# SDI-synchro-drive.net
KiCad netlist of a schematic drawn in EAGLE
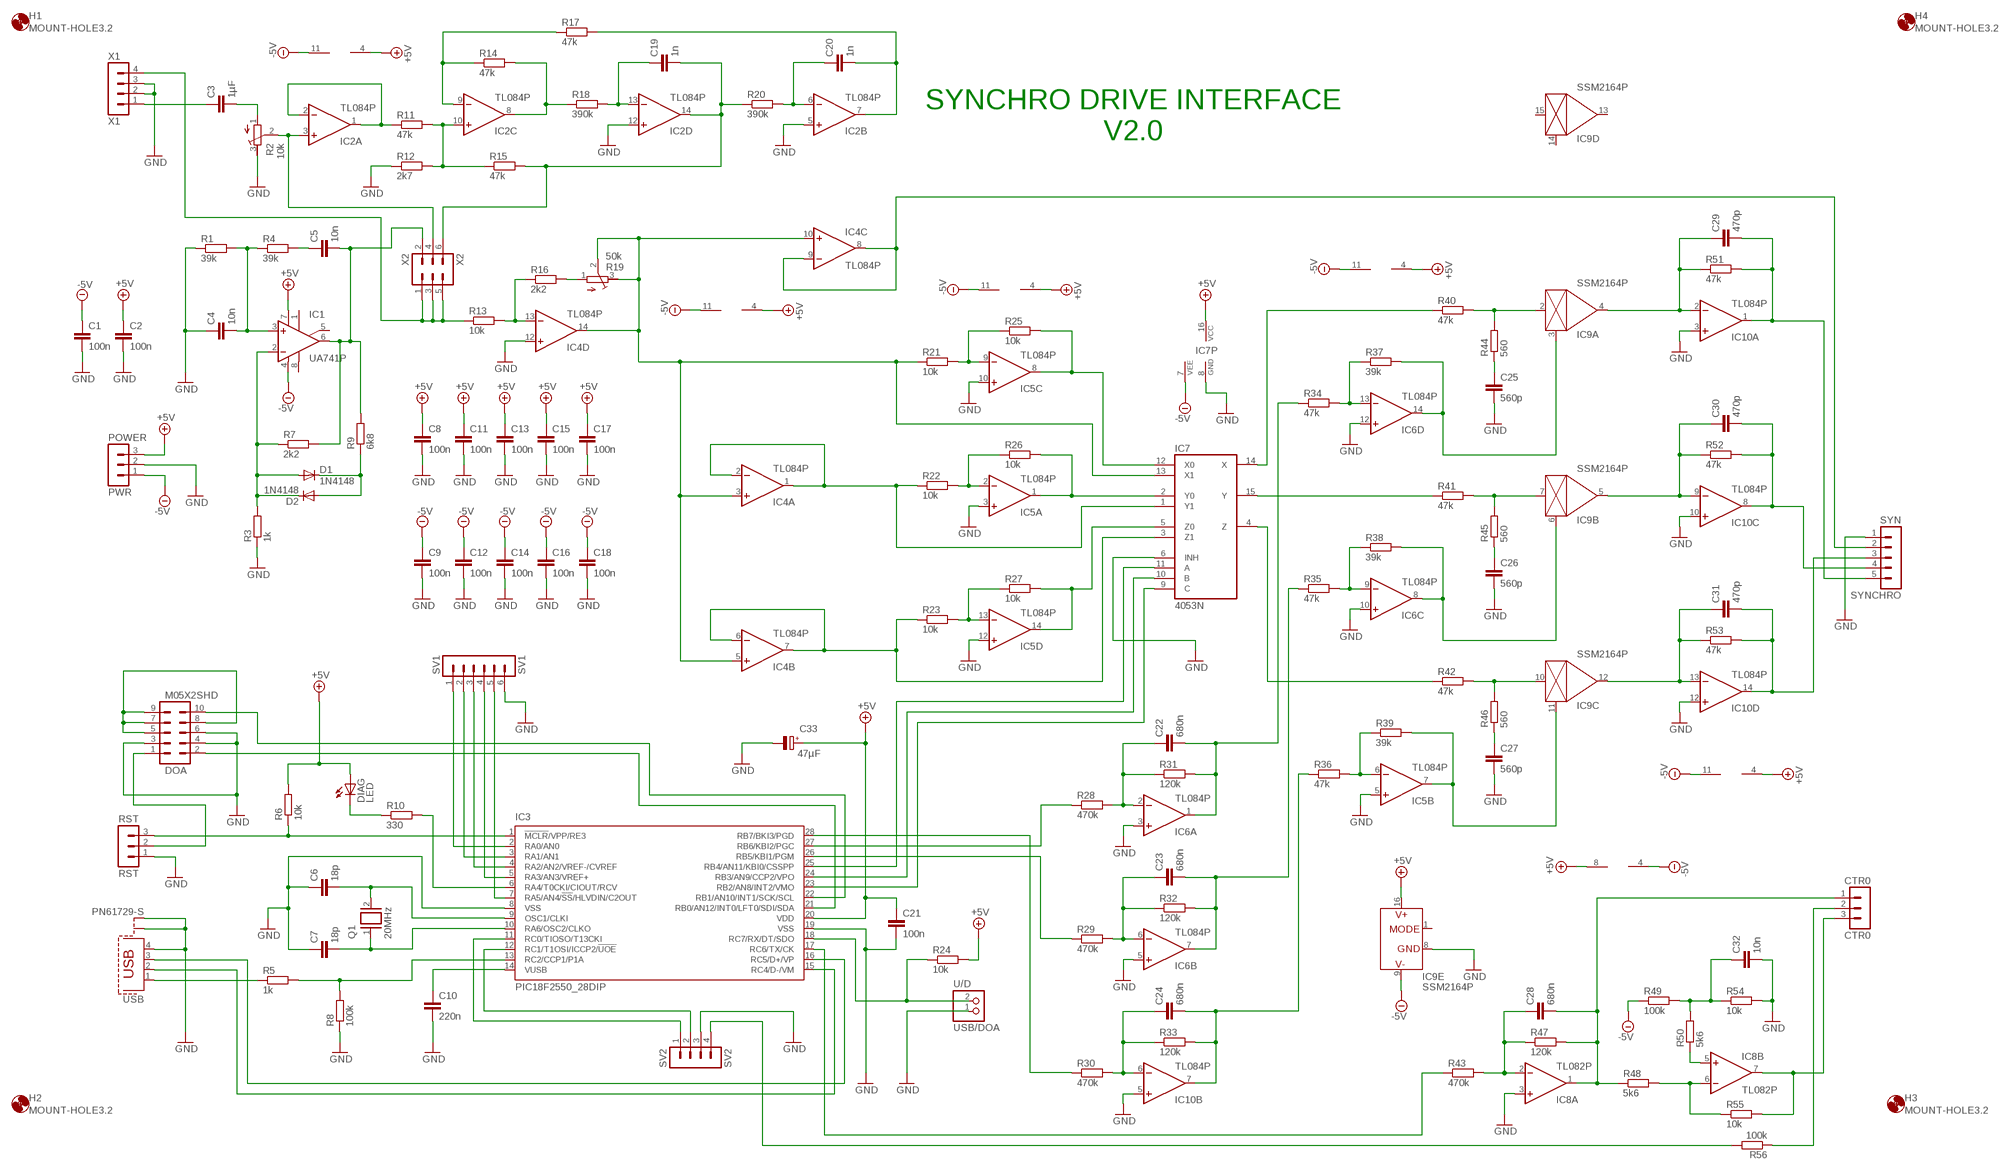
[diagram p0: schematic, sheet 1]

(export (version "E")
  (design (tool "Eeschema 10.0.6"))
  (components
    (comp (ref "C1")
      (value "100n")
      (footprint "eagle-import:C025-025X050")
      (libsource (lib "eagle-import") (part "C-EU025-025X050"))
    )
    (comp (ref "C2")
      (value "100n")
      (footprint "eagle-import:C025-025X050")
      (libsource (lib "eagle-import") (part "C-EU025-025X050"))
    )
    (comp (ref "C3")
      (value "1µF")
      (footprint "eagle-import:C5B3")
      (libsource (lib "eagle-import") (part "C5/3"))
    )
    (comp (ref "C4")
      (value "10n")
      (footprint "eagle-import:C025-025X050")
      (libsource (lib "eagle-import") (part "C-EU025-025X050"))
    )
    (comp (ref "C5")
      (value "10n")
      (footprint "eagle-import:C025-025X050")
      (libsource (lib "eagle-import") (part "C-EU025-025X050"))
    )
    (comp (ref "C6")
      (value "18p")
      (footprint "eagle-import:C025-025X050")
      (libsource (lib "eagle-import") (part "C-EU025-025X050"))
    )
    (comp (ref "C7")
      (value "18p")
      (footprint "eagle-import:C025-025X050")
      (libsource (lib "eagle-import") (part "C-EU025-025X050"))
    )
    (comp (ref "C8")
      (value "100n")
      (footprint "eagle-import:C025-025X050")
      (libsource (lib "eagle-import") (part "C-EU025-025X050"))
    )
    (comp (ref "C9")
      (value "100n")
      (footprint "eagle-import:C025-025X050")
      (libsource (lib "eagle-import") (part "C-EU025-025X050"))
    )
    (comp (ref "C10")
      (value "220n")
      (footprint "eagle-import:C5B3")
      (libsource (lib "eagle-import") (part "C5/3"))
    )
    (comp (ref "C11")
      (value "100n")
      (footprint "eagle-import:C025-025X050")
      (libsource (lib "eagle-import") (part "C-EU025-025X050"))
    )
    (comp (ref "C12")
      (value "100n")
      (footprint "eagle-import:C025-025X050")
      (libsource (lib "eagle-import") (part "C-EU025-025X050"))
    )
    (comp (ref "C13")
      (value "100n")
      (footprint "eagle-import:C025-025X050")
      (libsource (lib "eagle-import") (part "C-EU025-025X050"))
    )
    (comp (ref "C14")
      (value "100n")
      (footprint "eagle-import:C025-025X050")
      (libsource (lib "eagle-import") (part "C-EU025-025X050"))
    )
    (comp (ref "C15")
      (value "100n")
      (footprint "eagle-import:C025-025X050")
      (libsource (lib "eagle-import") (part "C-EU025-025X050"))
    )
    (comp (ref "C16")
      (value "100n")
      (footprint "eagle-import:C025-025X050")
      (libsource (lib "eagle-import") (part "C-EU025-025X050"))
    )
    (comp (ref "C17")
      (value "100n")
      (footprint "eagle-import:C025-025X050")
      (libsource (lib "eagle-import") (part "C-EU025-025X050"))
    )
    (comp (ref "C18")
      (value "100n")
      (footprint "eagle-import:C025-025X050")
      (libsource (lib "eagle-import") (part "C-EU025-025X050"))
    )
    (comp (ref "C19")
      (value "1n")
      (footprint "eagle-import:C025-025X050")
      (libsource (lib "eagle-import") (part "C-EU025-025X050"))
    )
    (comp (ref "C20")
      (value "1n")
      (footprint "eagle-import:C025-025X050")
      (libsource (lib "eagle-import") (part "C-EU025-025X050"))
    )
    (comp (ref "C21")
      (value "100n")
      (footprint "eagle-import:C025-025X050")
      (libsource (lib "eagle-import") (part "C-EU025-025X050"))
    )
    (comp (ref "C22")
      (value "680n")
      (footprint "eagle-import:C5B3")
      (libsource (lib "eagle-import") (part "C5/3"))
    )
    (comp (ref "C23")
      (value "680n")
      (footprint "eagle-import:C5B3")
      (libsource (lib "eagle-import") (part "C5/3"))
    )
    (comp (ref "C24")
      (value "680n")
      (footprint "eagle-import:C5B3")
      (libsource (lib "eagle-import") (part "C5/3"))
    )
    (comp (ref "C25")
      (value "560p")
      (footprint "eagle-import:C025-025X050")
      (libsource (lib "eagle-import") (part "C-EU025-025X050"))
    )
    (comp (ref "C26")
      (value "560p")
      (footprint "eagle-import:C025-025X050")
      (libsource (lib "eagle-import") (part "C-EU025-025X050"))
    )
    (comp (ref "C27")
      (value "560p")
      (footprint "eagle-import:C025-025X050")
      (libsource (lib "eagle-import") (part "C-EU025-025X050"))
    )
    (comp (ref "C28")
      (value "680n")
      (footprint "eagle-import:C5B3")
      (libsource (lib "eagle-import") (part "C5/3"))
    )
    (comp (ref "C29")
      (value "470p")
      (footprint "eagle-import:C025-025X050")
      (libsource (lib "eagle-import") (part "C-EU025-025X050"))
    )
    (comp (ref "C30")
      (value "470p")
      (footprint "eagle-import:C025-025X050")
      (libsource (lib "eagle-import") (part "C-EU025-025X050"))
    )
    (comp (ref "C31")
      (value "470p")
      (footprint "eagle-import:C025-025X050")
      (libsource (lib "eagle-import") (part "C-EU025-025X050"))
    )
    (comp (ref "C32")
      (value "10n")
      (footprint "eagle-import:C025-025X050")
      (libsource (lib "eagle-import") (part "C-EU025-025X050"))
    )
    (comp (ref "C33")
      (value "47µF")
      (footprint "eagle-import:E2,5-6")
      (libsource (lib "eagle-import") (part "CPOL-EUE2.5-6"))
    )
    (comp (ref "CTR0")
      (value "CTR0")
      (footprint "eagle-import:MA03-1")
      (libsource (lib "eagle-import") (part "MA03-1"))
    )
    (comp (ref "D1")
      (value "1N4148")
      (footprint "eagle-import:DO35-7")
      (libsource (lib "eagle-import") (part "1N4148DO35-7"))
    )
    (comp (ref "D2")
      (value "1N4148")
      (footprint "eagle-import:DO35-7")
      (libsource (lib "eagle-import") (part "1N4148DO35-7"))
    )
    (comp (ref "DIAG")
      (value "LED")
      (footprint "eagle-import:LED3MM")
      (libsource (lib "eagle-import") (part "LED3MM"))
    )
    (comp (ref "DOA")
      (value "M05X2SHD")
      (footprint "eagle-import:2X5-SHROUDED")
      (libsource (lib "eagle-import") (part "M05X2SHD"))
    )
    (comp (ref "H1")
      (value "MOUNT-HOLE3.2")
      (footprint "eagle-import:3,2")
      (libsource (lib "eagle-import") (part "MOUNT-HOLE3.2"))
    )
    (comp (ref "H2")
      (value "MOUNT-HOLE3.2")
      (footprint "eagle-import:3,2")
      (libsource (lib "eagle-import") (part "MOUNT-HOLE3.2"))
    )
    (comp (ref "H3")
      (value "MOUNT-HOLE3.2")
      (footprint "eagle-import:3,2")
      (libsource (lib "eagle-import") (part "MOUNT-HOLE3.2"))
    )
    (comp (ref "H4")
      (value "MOUNT-HOLE3.2")
      (footprint "eagle-import:3,2")
      (libsource (lib "eagle-import") (part "MOUNT-HOLE3.2"))
    )
    (comp (ref "IC1")
      (value "UA741P")
      (footprint "eagle-import:DIL08")
      (libsource (lib "eagle-import") (part "741PUA"))
    )
    (comp (ref "IC2")
      (value "TL084P")
      (footprint "eagle-import:DIL14")
      (libsource (lib "eagle-import") (part "TL084P"))
    )
    (comp (ref "IC3")
      (value "PIC18F2550_28DIP")
      (footprint "eagle-import:DIL28-3")
      (fields (field (name "MF") "MICROCHIP") (field (name "MPN") "PIC18F2550-I/SP"))
      (libsource (lib "eagle-import") (part "PIC18F2_28DIP550"))
    )
    (comp (ref "IC4")
      (value "TL084P")
      (footprint "eagle-import:DIL14")
      (libsource (lib "eagle-import") (part "TL084P"))
    )
    (comp (ref "IC5")
      (value "TL084P")
      (footprint "eagle-import:DIL14")
      (libsource (lib "eagle-import") (part "TL084P"))
    )
    (comp (ref "IC6")
      (value "TL084P")
      (footprint "eagle-import:DIL14")
      (libsource (lib "eagle-import") (part "TL084P"))
    )
    (comp (ref "IC7")
      (value "4053N")
      (footprint "eagle-import:DIL16")
      (libsource (lib "eagle-import") (part "4053N"))
    )
    (comp (ref "IC8")
      (value "TL082P")
      (footprint "eagle-import:DIL08")
      (libsource (lib "eagle-import") (part "TL082P"))
    )
    (comp (ref "IC9")
      (value "SSM2164P")
      (footprint "eagle-import:DIL16")
      (libsource (lib "eagle-import") (part "SSM2164P"))
    )
    (comp (ref "IC10")
      (value "TL084P")
      (footprint "eagle-import:DIL14")
      (libsource (lib "eagle-import") (part "TL084P"))
    )
    (comp (ref "POWER")
      (value "PWR")
      (footprint "eagle-import:MA03-1")
      (libsource (lib "eagle-import") (part "MA03-1"))
    )
    (comp (ref "Q1")
      (value "20MHz")
      (footprint "eagle-import:QS")
      (libsource (lib "eagle-import") (part "XTAL/S"))
    )
    (comp (ref "R1")
      (value "39k")
      (footprint "eagle-import:0204_7")
      (libsource (lib "eagle-import") (part "R-EU_0204/7"))
    )
    (comp (ref "R2")
      (value "10k")
      (footprint "eagle-import:RTRIM3299W")
      (libsource (lib "eagle-import") (part "R-TRIMM3299W"))
    )
    (comp (ref "R3")
      (value "1k")
      (footprint "eagle-import:0204_7")
      (libsource (lib "eagle-import") (part "R-EU_0204/7"))
    )
    (comp (ref "R4")
      (value "39k")
      (footprint "eagle-import:0204_7")
      (libsource (lib "eagle-import") (part "R-EU_0204/7"))
    )
    (comp (ref "R5")
      (value "1k")
      (footprint "eagle-import:0204_7")
      (libsource (lib "eagle-import") (part "R-EU_0204/7"))
    )
    (comp (ref "R6")
      (value "10k")
      (footprint "eagle-import:0204_7")
      (libsource (lib "eagle-import") (part "R-EU_0204/7"))
    )
    (comp (ref "R7")
      (value "2k2")
      (footprint "eagle-import:0204_7")
      (libsource (lib "eagle-import") (part "R-EU_0204/7"))
    )
    (comp (ref "R8")
      (value "100k")
      (footprint "eagle-import:0204_7")
      (libsource (lib "eagle-import") (part "R-EU_0204/7"))
    )
    (comp (ref "R9")
      (value "6k8")
      (footprint "eagle-import:0204_7")
      (libsource (lib "eagle-import") (part "R-EU_0204/7"))
    )
    (comp (ref "R10")
      (value "330")
      (footprint "eagle-import:0204_7")
      (libsource (lib "eagle-import") (part "R-EU_0204/7"))
    )
    (comp (ref "R11")
      (value "47k")
      (footprint "eagle-import:0204_7")
      (libsource (lib "eagle-import") (part "R-EU_0204/7"))
    )
    (comp (ref "R12")
      (value "2k7")
      (footprint "eagle-import:0204_7")
      (libsource (lib "eagle-import") (part "R-EU_0204/7"))
    )
    (comp (ref "R13")
      (value "10k")
      (footprint "eagle-import:0204_7")
      (libsource (lib "eagle-import") (part "R-EU_0204/7"))
    )
    (comp (ref "R14")
      (value "47k")
      (footprint "eagle-import:0204_7")
      (libsource (lib "eagle-import") (part "R-EU_0204/7"))
    )
    (comp (ref "R15")
      (value "47k")
      (footprint "eagle-import:0204_7")
      (libsource (lib "eagle-import") (part "R-EU_0204/7"))
    )
    (comp (ref "R16")
      (value "2k2")
      (footprint "eagle-import:0204_7")
      (libsource (lib "eagle-import") (part "R-EU_0204/7"))
    )
    (comp (ref "R17")
      (value "47k")
      (footprint "eagle-import:0204_7")
      (libsource (lib "eagle-import") (part "R-EU_0204/7"))
    )
    (comp (ref "R18")
      (value "390k")
      (footprint "eagle-import:0204_7")
      (libsource (lib "eagle-import") (part "R-EU_0204/7"))
    )
    (comp (ref "R19")
      (value "50k")
      (footprint "eagle-import:RTRIM3299W")
      (libsource (lib "eagle-import") (part "R-TRIMM3299W"))
    )
    (comp (ref "R20")
      (value "390k")
      (footprint "eagle-import:0204_7")
      (libsource (lib "eagle-import") (part "R-EU_0204/7"))
    )
    (comp (ref "R21")
      (value "10k")
      (footprint "eagle-import:0204_7")
      (libsource (lib "eagle-import") (part "R-EU_0204/7"))
    )
    (comp (ref "R22")
      (value "10k")
      (footprint "eagle-import:0204_7")
      (libsource (lib "eagle-import") (part "R-EU_0204/7"))
    )
    (comp (ref "R23")
      (value "10k")
      (footprint "eagle-import:0204_7")
      (libsource (lib "eagle-import") (part "R-EU_0204/7"))
    )
    (comp (ref "R24")
      (value "10k")
      (footprint "eagle-import:0204_7")
      (libsource (lib "eagle-import") (part "R-EU_0204/7"))
    )
    (comp (ref "R25")
      (value "10k")
      (footprint "eagle-import:0204_7")
      (libsource (lib "eagle-import") (part "R-EU_0204/7"))
    )
    (comp (ref "R26")
      (value "10k")
      (footprint "eagle-import:0204_7")
      (libsource (lib "eagle-import") (part "R-EU_0204/7"))
    )
    (comp (ref "R27")
      (value "10k")
      (footprint "eagle-import:0204_7")
      (libsource (lib "eagle-import") (part "R-EU_0204/7"))
    )
    (comp (ref "R28")
      (value "470k")
      (footprint "eagle-import:0204_7")
      (libsource (lib "eagle-import") (part "R-EU_0204/7"))
    )
    (comp (ref "R29")
      (value "470k")
      (footprint "eagle-import:0204_7")
      (libsource (lib "eagle-import") (part "R-EU_0204/7"))
    )
    (comp (ref "R30")
      (value "470k")
      (footprint "eagle-import:0204_7")
      (libsource (lib "eagle-import") (part "R-EU_0204/7"))
    )
    (comp (ref "R31")
      (value "120k")
      (footprint "eagle-import:0204_7")
      (libsource (lib "eagle-import") (part "R-EU_0204/7"))
    )
    (comp (ref "R32")
      (value "120k")
      (footprint "eagle-import:0204_7")
      (libsource (lib "eagle-import") (part "R-EU_0204/7"))
    )
    (comp (ref "R33")
      (value "120k")
      (footprint "eagle-import:0204_7")
      (libsource (lib "eagle-import") (part "R-EU_0204/7"))
    )
    (comp (ref "R34")
      (value "47k")
      (footprint "eagle-import:0204_7")
      (libsource (lib "eagle-import") (part "R-EU_0204/7"))
    )
    (comp (ref "R35")
      (value "47k")
      (footprint "eagle-import:0204_7")
      (libsource (lib "eagle-import") (part "R-EU_0204/7"))
    )
    (comp (ref "R36")
      (value "47k")
      (footprint "eagle-import:0204_7")
      (libsource (lib "eagle-import") (part "R-EU_0204/7"))
    )
    (comp (ref "R37")
      (value "39k")
      (footprint "eagle-import:0204_7")
      (libsource (lib "eagle-import") (part "R-EU_0204/7"))
    )
    (comp (ref "R38")
      (value "39k")
      (footprint "eagle-import:0204_7")
      (libsource (lib "eagle-import") (part "R-EU_0204/7"))
    )
    (comp (ref "R39")
      (value "39k")
      (footprint "eagle-import:0204_7")
      (libsource (lib "eagle-import") (part "R-EU_0204/7"))
    )
    (comp (ref "R40")
      (value "47k")
      (footprint "eagle-import:0204_7")
      (libsource (lib "eagle-import") (part "R-EU_0204/7"))
    )
    (comp (ref "R41")
      (value "47k")
      (footprint "eagle-import:0204_7")
      (libsource (lib "eagle-import") (part "R-EU_0204/7"))
    )
    (comp (ref "R42")
      (value "47k")
      (footprint "eagle-import:0204_7")
      (libsource (lib "eagle-import") (part "R-EU_0204/7"))
    )
    (comp (ref "R43")
      (value "470k")
      (footprint "eagle-import:0204_7")
      (libsource (lib "eagle-import") (part "R-EU_0204/7"))
    )
    (comp (ref "R44")
      (value "560")
      (footprint "eagle-import:0204_7")
      (libsource (lib "eagle-import") (part "R-EU_0204/7"))
    )
    (comp (ref "R45")
      (value "560")
      (footprint "eagle-import:0204_7")
      (libsource (lib "eagle-import") (part "R-EU_0204/7"))
    )
    (comp (ref "R46")
      (value "560")
      (footprint "eagle-import:0204_7")
      (libsource (lib "eagle-import") (part "R-EU_0204/7"))
    )
    (comp (ref "R47")
      (value "120k")
      (footprint "eagle-import:0204_7")
      (libsource (lib "eagle-import") (part "R-EU_0204/7"))
    )
    (comp (ref "R48")
      (value "5k6")
      (footprint "eagle-import:0204_7")
      (libsource (lib "eagle-import") (part "R-EU_0204/7"))
    )
    (comp (ref "R49")
      (value "100k")
      (footprint "eagle-import:0204_7")
      (libsource (lib "eagle-import") (part "R-EU_0204/7"))
    )
    (comp (ref "R50")
      (value "5k6")
      (footprint "eagle-import:0204_7")
      (libsource (lib "eagle-import") (part "R-EU_0204/7"))
    )
    (comp (ref "R51")
      (value "47k")
      (footprint "eagle-import:0204_7")
      (libsource (lib "eagle-import") (part "R-EU_0204/7"))
    )
    (comp (ref "R52")
      (value "47k")
      (footprint "eagle-import:0204_7")
      (libsource (lib "eagle-import") (part "R-EU_0204/7"))
    )
    (comp (ref "R53")
      (value "47k")
      (footprint "eagle-import:0204_7")
      (libsource (lib "eagle-import") (part "R-EU_0204/7"))
    )
    (comp (ref "R54")
      (value "10k")
      (footprint "eagle-import:0204_7")
      (libsource (lib "eagle-import") (part "R-EU_0204/7"))
    )
    (comp (ref "R55")
      (value "10k")
      (footprint "eagle-import:0204_7")
      (libsource (lib "eagle-import") (part "R-EU_0204/7"))
    )
    (comp (ref "R56")
      (value "100k")
      (footprint "eagle-import:0204_7")
      (libsource (lib "eagle-import") (part "R-EU_0204/7"))
    )
    (comp (ref "RST")
      (value "RST")
      (footprint "eagle-import:MA03-1")
      (libsource (lib "eagle-import") (part "MA03-1"))
    )
    (comp (ref "SV1")
      (value "SV1")
      (footprint "eagle-import:MA06-1")
      (libsource (lib "eagle-import") (part "MA06-1"))
    )
    (comp (ref "SV2")
      (value "SV2")
      (footprint "eagle-import:MA04-1")
      (libsource (lib "eagle-import") (part "MA04-1"))
    )
    (comp (ref "SYNCHRO")
      (value "SYN")
      (footprint "eagle-import:MA05-1")
      (libsource (lib "eagle-import") (part "MA05-1"))
    )
    (comp (ref "USB")
      (value "PN61729-S")
      (footprint "eagle-import:PN61729-S")
      (libsource (lib "eagle-import") (part "PN61729-S"))
    )
    (comp (ref "USB/DOA")
      (value "U/D")
      (footprint "eagle-import:1X02")
      (libsource (lib "eagle-import") (part "PINHD-1X2"))
    )
    (comp (ref "X1")
      (value "X1")
      (footprint "eagle-import:MA04-1")
      (libsource (lib "eagle-import") (part "MA04-1"))
    )
    (comp (ref "X2")
      (value "X2")
      (footprint "eagle-import:MA03-2")
      (libsource (lib "eagle-import") (part "MA03-2"))
    )
  )
  (nets
    (net (code "1") (name "+5V") (class "Default")
      (node (ref "C11") (pin "1") (pinfunction "1_1") (pintype "passive"))
      (node (ref "C13") (pin "1") (pinfunction "1_1") (pintype "passive"))
      (node (ref "C15") (pin "1") (pinfunction "1_1") (pintype "passive"))
      (node (ref "C17") (pin "1") (pinfunction "1_1") (pintype "passive"))
      (node (ref "C2") (pin "1") (pinfunction "1_1") (pintype "passive"))
      (node (ref "C21") (pin "1") (pinfunction "1_1") (pintype "passive"))
      (node (ref "C33") (pin "+") (pinfunction "+_+") (pintype "passive"))
      (node (ref "C8") (pin "1") (pinfunction "1_1") (pintype "passive"))
      (node (ref "DIAG") (pin "A") (pinfunction "A_A") (pintype "passive"))
      (node (ref "IC1") (pin "7") (pinfunction "V+_7") (pintype "power_in"))
      (node (ref "IC10") (pin "4") (pinfunction "V+_4") (pintype "power_in"))
      (node (ref "IC2") (pin "4") (pinfunction "V+_4") (pintype "power_in"))
      (node (ref "IC3") (pin "20") (pinfunction "VDD_20") (pintype "power_in"))
      (node (ref "IC4") (pin "4") (pinfunction "V+_4") (pintype "power_in"))
      (node (ref "IC5") (pin "4") (pinfunction "V+_4") (pintype "power_in"))
      (node (ref "IC6") (pin "4") (pinfunction "V+_4") (pintype "power_in"))
      (node (ref "IC7") (pin "16") (pinfunction "VCC_16") (pintype "power_in"))
      (node (ref "IC8") (pin "8") (pinfunction "V+_8") (pintype "power_in"))
      (node (ref "IC9") (pin "16") (pinfunction "V+_16") (pintype "power_in"))
      (node (ref "POWER") (pin "3") (pinfunction "3_3") (pintype "passive"))
      (node (ref "R24") (pin "2") (pinfunction "2_2") (pintype "passive"))
      (node (ref "R6") (pin "2") (pinfunction "2_2") (pintype "passive"))
    )
    (net (code "2") (name "-5V") (class "Default")
      (node (ref "C1") (pin "1") (pinfunction "1_1") (pintype "passive"))
      (node (ref "C12") (pin "1") (pinfunction "1_1") (pintype "passive"))
      (node (ref "C14") (pin "1") (pinfunction "1_1") (pintype "passive"))
      (node (ref "C16") (pin "1") (pinfunction "1_1") (pintype "passive"))
      (node (ref "C18") (pin "1") (pinfunction "1_1") (pintype "passive"))
      (node (ref "C9") (pin "1") (pinfunction "1_1") (pintype "passive"))
      (node (ref "IC1") (pin "4") (pinfunction "V-_4") (pintype "power_in"))
      (node (ref "IC10") (pin "11") (pinfunction "V-_11") (pintype "power_in"))
      (node (ref "IC2") (pin "11") (pinfunction "V-_11") (pintype "power_in"))
      (node (ref "IC4") (pin "11") (pinfunction "V-_11") (pintype "power_in"))
      (node (ref "IC5") (pin "11") (pinfunction "V-_11") (pintype "power_in"))
      (node (ref "IC6") (pin "11") (pinfunction "V-_11") (pintype "power_in"))
      (node (ref "IC7") (pin "7") (pinfunction "VEE_7") (pintype "power_in"))
      (node (ref "IC8") (pin "4") (pinfunction "V-_4") (pintype "power_in"))
      (node (ref "IC9") (pin "9") (pinfunction "V-_9") (pintype "power_in"))
      (node (ref "POWER") (pin "1") (pinfunction "1_1") (pintype "passive"))
      (node (ref "R49") (pin "1") (pinfunction "1_1") (pintype "passive"))
    )
    (net (code "3") (name "GND") (class "Default")
      (node (ref "C1") (pin "2") (pinfunction "2_2") (pintype "passive"))
      (node (ref "C10") (pin "2") (pinfunction "2_2") (pintype "passive"))
      (node (ref "C11") (pin "2") (pinfunction "2_2") (pintype "passive"))
      (node (ref "C12") (pin "2") (pinfunction "2_2") (pintype "passive"))
      (node (ref "C13") (pin "2") (pinfunction "2_2") (pintype "passive"))
      (node (ref "C14") (pin "2") (pinfunction "2_2") (pintype "passive"))
      (node (ref "C15") (pin "2") (pinfunction "2_2") (pintype "passive"))
      (node (ref "C16") (pin "2") (pinfunction "2_2") (pintype "passive"))
      (node (ref "C17") (pin "2") (pinfunction "2_2") (pintype "passive"))
      (node (ref "C18") (pin "2") (pinfunction "2_2") (pintype "passive"))
      (node (ref "C2") (pin "2") (pinfunction "2_2") (pintype "passive"))
      (node (ref "C21") (pin "2") (pinfunction "2_2") (pintype "passive"))
      (node (ref "C25") (pin "2") (pinfunction "2_2") (pintype "passive"))
      (node (ref "C26") (pin "2") (pinfunction "2_2") (pintype "passive"))
      (node (ref "C27") (pin "2") (pinfunction "2_2") (pintype "passive"))
      (node (ref "C32") (pin "2") (pinfunction "2_2") (pintype "passive"))
      (node (ref "C33") (pin "-") (pinfunction "-_-") (pintype "passive"))
      (node (ref "C4") (pin "1") (pinfunction "1_1") (pintype "passive"))
      (node (ref "C6") (pin "1") (pinfunction "1_1") (pintype "passive"))
      (node (ref "C7") (pin "1") (pinfunction "1_1") (pintype "passive"))
      (node (ref "C8") (pin "2") (pinfunction "2_2") (pintype "passive"))
      (node (ref "C9") (pin "2") (pinfunction "2_2") (pintype "passive"))
      (node (ref "DOA") (pin "3") (pinfunction "3_3") (pintype "passive"))
      (node (ref "DOA") (pin "4") (pinfunction "4_4") (pintype "passive"))
      (node (ref "DOA") (pin "6") (pinfunction "6_6") (pintype "passive"))
      (node (ref "IC10") (pin "10") (pinfunction "+IN_10") (pintype "input"))
      (node (ref "IC10") (pin "12") (pinfunction "+IN_12") (pintype "input"))
      (node (ref "IC10") (pin "3") (pinfunction "+IN_3") (pintype "input"))
      (node (ref "IC10") (pin "5") (pinfunction "+IN_5") (pintype "input"))
      (node (ref "IC2") (pin "12") (pinfunction "+IN_12") (pintype "input"))
      (node (ref "IC2") (pin "5") (pinfunction "+IN_5") (pintype "input"))
      (node (ref "IC3") (pin "19") (pinfunction "VSS_19") (pintype "power_in"))
      (node (ref "IC3") (pin "8") (pinfunction "VSS_8") (pintype "power_in"))
      (node (ref "IC4") (pin "12") (pinfunction "+IN_12") (pintype "input"))
      (node (ref "IC5") (pin "10") (pinfunction "+IN_10") (pintype "input"))
      (node (ref "IC5") (pin "12") (pinfunction "+IN_12") (pintype "input"))
      (node (ref "IC5") (pin "3") (pinfunction "+IN_3") (pintype "input"))
      (node (ref "IC5") (pin "5") (pinfunction "+IN_5") (pintype "input"))
      (node (ref "IC6") (pin "10") (pinfunction "+IN_10") (pintype "input"))
      (node (ref "IC6") (pin "12") (pinfunction "+IN_12") (pintype "input"))
      (node (ref "IC6") (pin "3") (pinfunction "+IN_3") (pintype "input"))
      (node (ref "IC6") (pin "5") (pinfunction "+IN_5") (pintype "input"))
      (node (ref "IC7") (pin "6") (pinfunction "INH_6") (pintype "input"))
      (node (ref "IC7") (pin "8") (pinfunction "GND_8") (pintype "power_in"))
      (node (ref "IC8") (pin "3") (pinfunction "+IN_3") (pintype "input"))
      (node (ref "IC9") (pin "8") (pinfunction "GND_8") (pintype "power_in"))
      (node (ref "POWER") (pin "2") (pinfunction "2_2") (pintype "passive"))
      (node (ref "R1") (pin "1") (pinfunction "1_1") (pintype "passive"))
      (node (ref "R12") (pin "1") (pinfunction "1_1") (pintype "passive"))
      (node (ref "R2") (pin "3") (pinfunction "A_3") (pintype "passive"))
      (node (ref "R3") (pin "1") (pinfunction "1_1") (pintype "passive"))
      (node (ref "R54") (pin "2") (pinfunction "2_2") (pintype "passive"))
      (node (ref "R8") (pin "1") (pinfunction "1_1") (pintype "passive"))
      (node (ref "RST") (pin "1") (pinfunction "1_1") (pintype "passive"))
      (node (ref "SV1") (pin "6") (pinfunction "6_6") (pintype "passive"))
      (node (ref "SV2") (pin "3") (pinfunction "3_3") (pintype "passive"))
      (node (ref "SYNCHRO") (pin "1") (pinfunction "1_1") (pintype "passive"))
      (node (ref "USB") (pin "4") (pinfunction "4_4") (pintype "passive"))
      (node (ref "USB") (pin "S1") (pinfunction "S1_S1") (pintype "passive"))
      (node (ref "USB") (pin "S2") (pinfunction "S2_S2") (pintype "passive"))
      (node (ref "USB/DOA") (pin "1") (pinfunction "1_1") (pintype "passive"))
      (node (ref "X1") (pin "2") (pinfunction "2_2") (pintype "passive"))
      (node (ref "X1") (pin "3") (pinfunction "3_3") (pintype "passive"))
    )
    (net (code "4") (name "Net-(C3-Pad1)") (class "Default")
      (node (ref "C3") (pin "1") (pinfunction "1_1") (pintype "passive"))
      (node (ref "X1") (pin "1") (pinfunction "1_1") (pintype "passive"))
    )
    (net (code "5") (name "Net-(C5-Pad1)") (class "Default")
      (node (ref "C5") (pin "1") (pinfunction "1_1") (pintype "passive"))
      (node (ref "R4") (pin "2") (pinfunction "2_2") (pintype "passive"))
    )
    (net (code "6") (name "Net-(C25-Pad1)") (class "Default")
      (node (ref "C25") (pin "1") (pinfunction "1_1") (pintype "passive"))
      (node (ref "R44") (pin "1") (pinfunction "1_1") (pintype "passive"))
    )
    (net (code "7") (name "Net-(C26-Pad1)") (class "Default")
      (node (ref "C26") (pin "1") (pinfunction "1_1") (pintype "passive"))
      (node (ref "R45") (pin "1") (pinfunction "1_1") (pintype "passive"))
    )
    (net (code "8") (name "Net-(C27-Pad1)") (class "Default")
      (node (ref "C27") (pin "1") (pinfunction "1_1") (pintype "passive"))
      (node (ref "R46") (pin "1") (pinfunction "1_1") (pintype "passive"))
    )
    (net (code "9") (name "Net-(C32-Pad1)") (class "Default")
      (node (ref "C32") (pin "1") (pinfunction "1_1") (pintype "passive"))
      (node (ref "R49") (pin "2") (pinfunction "2_2") (pintype "passive"))
      (node (ref "R50") (pin "2") (pinfunction "2_2") (pintype "passive"))
      (node (ref "R54") (pin "1") (pinfunction "1_1") (pintype "passive"))
    )
    (net (code "10") (name "Net-(CTR0-Pad2)") (class "Default")
      (node (ref "CTR0") (pin "2") (pinfunction "2_2") (pintype "passive"))
      (node (ref "R56") (pin "1") (pinfunction "1_1") (pintype "passive"))
    )
    (net (code "11") (name "Net-(D1-PadC)") (class "Default")
      (node (ref "D1") (pin "C") (pinfunction "C_C") (pintype "passive"))
      (node (ref "D2") (pin "A") (pinfunction "A_A") (pintype "passive"))
      (node (ref "R9") (pin "1") (pinfunction "1_1") (pintype "passive"))
    )
    (net (code "12") (name "Net-(DIAG-C)") (class "Default")
      (node (ref "DIAG") (pin "K") (pinfunction "C_K") (pintype "passive"))
      (node (ref "R10") (pin "1") (pinfunction "1_1") (pintype "passive"))
    )
    (net (code "13") (name "Net-(DOA-Pad1)") (class "Default")
      (node (ref "DOA") (pin "1") (pinfunction "1_1") (pintype "passive"))
      (node (ref "RST") (pin "2") (pinfunction "2_2") (pintype "passive"))
    )
    (net (code "14") (name "Net-(DOA-Pad5)") (class "Default")
      (node (ref "DOA") (pin "5") (pinfunction "5_5") (pintype "passive"))
      (node (ref "DOA") (pin "7") (pinfunction "7_7") (pintype "passive"))
      (node (ref "DOA") (pin "8") (pinfunction "8_8") (pintype "passive"))
      (node (ref "DOA") (pin "9") (pinfunction "9_9") (pintype "passive"))
    )
    (net (code "15") (name "Net-(IC1-+IN)") (class "Default")
      (node (ref "C4") (pin "2") (pinfunction "2_2") (pintype "passive"))
      (node (ref "IC1") (pin "3") (pinfunction "+IN_3") (pintype "input"))
      (node (ref "R1") (pin "2") (pinfunction "2_2") (pintype "passive"))
      (node (ref "R4") (pin "1") (pinfunction "1_1") (pintype "passive"))
    )
    (net (code "16") (name "Net-(IC1--IN)") (class "Default")
      (node (ref "D1") (pin "A") (pinfunction "A_A") (pintype "passive"))
      (node (ref "D2") (pin "C") (pinfunction "C_C") (pintype "passive"))
      (node (ref "IC1") (pin "2") (pinfunction "-IN_2") (pintype "input"))
      (node (ref "R3") (pin "2") (pinfunction "2_2") (pintype "passive"))
      (node (ref "R7") (pin "1") (pinfunction "1_1") (pintype "passive"))
    )
    (net (code "17") (name "Net-(IC1-OUT)") (class "Default")
      (node (ref "C5") (pin "2") (pinfunction "2_2") (pintype "passive"))
      (node (ref "IC1") (pin "6") (pinfunction "OUT_6") (pintype "output"))
      (node (ref "R7") (pin "2") (pinfunction "2_2") (pintype "passive"))
      (node (ref "R9") (pin "2") (pinfunction "2_2") (pintype "passive"))
      (node (ref "X2") (pin "2") (pinfunction "2_2") (pintype "passive"))
    )
    (net (code "18") (name "Net-(IC2A-+IN)") (class "Default")
      (node (ref "IC2") (pin "3") (pinfunction "+IN_3") (pintype "input"))
      (node (ref "R2") (pin "2") (pinfunction "S_2") (pintype "passive"))
      (node (ref "X2") (pin "4") (pinfunction "4_4") (pintype "passive"))
    )
    (net (code "19") (name "Net-(IC2A--IN)") (class "Default")
      (node (ref "IC2") (pin "1") (pinfunction "OUT_1") (pintype "output"))
      (node (ref "IC2") (pin "2") (pinfunction "-IN_2") (pintype "input"))
      (node (ref "R11") (pin "1") (pinfunction "1_1") (pintype "passive"))
    )
    (net (code "20") (name "Net-(IC2B--IN)") (class "Default")
      (node (ref "C20") (pin "1") (pinfunction "1_1") (pintype "passive"))
      (node (ref "IC2") (pin "6") (pinfunction "-IN_6") (pintype "input"))
      (node (ref "R20") (pin "2") (pinfunction "2_2") (pintype "passive"))
    )
    (net (code "21") (name "Net-(IC2B-OUT)") (class "Default")
      (node (ref "C20") (pin "2") (pinfunction "2_2") (pintype "passive"))
      (node (ref "IC2") (pin "7") (pinfunction "OUT_7") (pintype "output"))
      (node (ref "R17") (pin "2") (pinfunction "2_2") (pintype "passive"))
    )
    (net (code "22") (name "Net-(IC2C-+IN)") (class "Default")
      (node (ref "IC2") (pin "10") (pinfunction "+IN_10") (pintype "input"))
      (node (ref "R11") (pin "2") (pinfunction "2_2") (pintype "passive"))
      (node (ref "R12") (pin "2") (pinfunction "2_2") (pintype "passive"))
      (node (ref "R15") (pin "1") (pinfunction "1_1") (pintype "passive"))
    )
    (net (code "23") (name "Net-(IC2C--IN)") (class "Default")
      (node (ref "IC2") (pin "9") (pinfunction "-IN_9") (pintype "input"))
      (node (ref "R14") (pin "1") (pinfunction "1_1") (pintype "passive"))
      (node (ref "R17") (pin "1") (pinfunction "1_1") (pintype "passive"))
    )
    (net (code "24") (name "Net-(IC2C-OUT)") (class "Default")
      (node (ref "IC2") (pin "8") (pinfunction "OUT_8") (pintype "output"))
      (node (ref "R14") (pin "2") (pinfunction "2_2") (pintype "passive"))
      (node (ref "R18") (pin "1") (pinfunction "1_1") (pintype "passive"))
    )
    (net (code "25") (name "Net-(IC2D--IN)") (class "Default")
      (node (ref "C19") (pin "1") (pinfunction "1_1") (pintype "passive"))
      (node (ref "IC2") (pin "13") (pinfunction "-IN_13") (pintype "input"))
      (node (ref "R18") (pin "2") (pinfunction "2_2") (pintype "passive"))
    )
    (net (code "26") (name "Net-(IC2D-OUT)") (class "Default")
      (node (ref "C19") (pin "2") (pinfunction "2_2") (pintype "passive"))
      (node (ref "IC2") (pin "14") (pinfunction "OUT_14") (pintype "output"))
      (node (ref "R15") (pin "2") (pinfunction "2_2") (pintype "passive"))
      (node (ref "R20") (pin "1") (pinfunction "1_1") (pintype "passive"))
      (node (ref "X2") (pin "6") (pinfunction "6_6") (pintype "passive"))
    )
    (net (code "27") (name "Net-(IC3-OSC1{slash}CLKI)") (class "Default")
      (node (ref "C6") (pin "2") (pinfunction "2_2") (pintype "passive"))
      (node (ref "IC3") (pin "9") (pinfunction "OSC1/CLKI_9") (pintype "input"))
      (node (ref "Q1") (pin "2") (pinfunction "2_2") (pintype "passive"))
    )
    (net (code "28") (name "Net-(IC3-RA0{slash}AN0)") (class "Default")
      (node (ref "IC3") (pin "2") (pinfunction "RA0/AN0_2") (pintype "bidirectional"))
      (node (ref "SV1") (pin "1") (pinfunction "1_1") (pintype "passive"))
    )
    (net (code "29") (name "Net-(IC3-RA1{slash}AN1)") (class "Default")
      (node (ref "IC3") (pin "3") (pinfunction "RA1/AN1_3") (pintype "bidirectional"))
      (node (ref "SV1") (pin "2") (pinfunction "2_2") (pintype "passive"))
    )
    (net (code "30") (name "Net-(IC3-RA2{slash}AN2{slash}VREF-{slash}CVREF)") (class "Default")
      (node (ref "IC3") (pin "4") (pinfunction "RA2/AN2/VREF-/CVREF_4") (pintype "bidirectional"))
      (node (ref "SV1") (pin "3") (pinfunction "3_3") (pintype "passive"))
    )
    (net (code "31") (name "Net-(IC3-RA3{slash}AN3{slash}VREF+)") (class "Default")
      (node (ref "IC3") (pin "5") (pinfunction "RA3/AN3/VREF+_5") (pintype "bidirectional"))
      (node (ref "SV1") (pin "4") (pinfunction "4_4") (pintype "passive"))
    )
    (net (code "32") (name "Net-(IC3-RA4{slash}T0CKI{slash}CIOUT{slash}RCV)") (class "Default")
      (node (ref "IC3") (pin "6") (pinfunction "RA4/T0CKI/CIOUT/RCV_6") (pintype "bidirectional"))
      (node (ref "R10") (pin "2") (pinfunction "2_2") (pintype "passive"))
    )
    (net (code "33") (name "Net-(IC3-RA5{slash}AN4{slash}~{SS}{slash}HLVDIN{slash}C2OUT)") (class "Default")
      (node (ref "IC3") (pin "7") (pinfunction "RA5/AN4/~{SS}/HLVDIN/C2OUT_7") (pintype "bidirectional"))
      (node (ref "SV1") (pin "5") (pinfunction "5_5") (pintype "passive"))
    )
    (net (code "34") (name "Net-(IC3-RA6{slash}OSC2{slash}CLKO)") (class "Default")
      (node (ref "C7") (pin "2") (pinfunction "2_2") (pintype "passive"))
      (node (ref "IC3") (pin "10") (pinfunction "RA6/OSC2/CLKO_10") (pintype "output"))
      (node (ref "Q1") (pin "1") (pinfunction "1_1") (pintype "passive"))
    )
    (net (code "35") (name "Net-(IC3-RB0{slash}AN12{slash}INT0{slash}LFT0{slash}SDI{slash}SDA)") (class "Default")
      (node (ref "DOA") (pin "2") (pinfunction "2_2") (pintype "passive"))
      (node (ref "IC3") (pin "21") (pinfunction "RB0/AN12/INT0/LFT0/SDI/SDA_21") (pintype "bidirectional"))
    )
    (net (code "36") (name "Net-(IC3-RB1{slash}AN10{slash}INT1{slash}SCK{slash}SCL)") (class "Default")
      (node (ref "DOA") (pin "10") (pinfunction "10_10") (pintype "passive"))
      (node (ref "IC3") (pin "22") (pinfunction "RB1/AN10/INT1/SCK/SCL_22") (pintype "bidirectional"))
    )
    (net (code "37") (name "Net-(IC3-RB2{slash}AN8{slash}INT2{slash}VMO)") (class "Default")
      (node (ref "IC3") (pin "23") (pinfunction "RB2/AN8/INT2/VMO_23") (pintype "bidirectional"))
      (node (ref "IC7") (pin "9") (pinfunction "C_9") (pintype "input"))
    )
    (net (code "38") (name "Net-(IC3-RB3{slash}AN9{slash}CCP2{slash}VPO)") (class "Default")
      (node (ref "IC3") (pin "24") (pinfunction "RB3/AN9/CCP2/VPO_24") (pintype "bidirectional"))
      (node (ref "IC7") (pin "10") (pinfunction "B_10") (pintype "input"))
    )
    (net (code "39") (name "Net-(IC3-RB4{slash}AN11{slash}KBI0{slash}CSSPP)") (class "Default")
      (node (ref "IC3") (pin "25") (pinfunction "RB4/AN11/KBI0/CSSPP_25") (pintype "bidirectional"))
      (node (ref "IC7") (pin "11") (pinfunction "A_11") (pintype "input"))
    )
    (net (code "40") (name "Net-(IC3-RB5{slash}KBI1{slash}PGM)") (class "Default")
      (node (ref "IC3") (pin "26") (pinfunction "RB5/KBI1/PGM_26") (pintype "bidirectional"))
      (node (ref "R29") (pin "1") (pinfunction "1_1") (pintype "passive"))
    )
    (net (code "41") (name "Net-(IC3-RB6{slash}KBI2{slash}PGC)") (class "Default")
      (node (ref "IC3") (pin "27") (pinfunction "RB6/KBI2/PGC_27") (pintype "bidirectional"))
      (node (ref "R28") (pin "1") (pinfunction "1_1") (pintype "passive"))
    )
    (net (code "42") (name "Net-(IC3-RB7{slash}BKI3{slash}PGD)") (class "Default")
      (node (ref "IC3") (pin "28") (pinfunction "RB7/BKI3/PGD_28") (pintype "bidirectional"))
      (node (ref "R30") (pin "1") (pinfunction "1_1") (pintype "passive"))
    )
    (net (code "43") (name "Net-(IC3-RC0{slash}TIOSO{slash}T13CKI)") (class "Default")
      (node (ref "IC3") (pin "11") (pinfunction "RC0/TIOSO/T13CKI_11") (pintype "bidirectional"))
      (node (ref "SV2") (pin "1") (pinfunction "1_1") (pintype "passive"))
    )
    (net (code "44") (name "Net-(IC3-RC1{slash}T1OSI{slash}ICCP2{slash}~{UOE})") (class "Default")
      (node (ref "IC3") (pin "12") (pinfunction "RC1/T1OSI/ICCP2/~{UOE}_12") (pintype "bidirectional"))
      (node (ref "SV2") (pin "2") (pinfunction "2_2") (pintype "passive"))
    )
    (net (code "45") (name "Net-(IC3-RC2{slash}CCP1{slash}P1A)") (class "Default")
      (node (ref "IC3") (pin "13") (pinfunction "RC2/CCP1/P1A_13") (pintype "bidirectional"))
      (node (ref "R5") (pin "2") (pinfunction "2_2") (pintype "passive"))
      (node (ref "R8") (pin "2") (pinfunction "2_2") (pintype "passive"))
    )
    (net (code "46") (name "Net-(IC3-RC4{slash}D-{slash}VM)") (class "Default")
      (node (ref "IC3") (pin "15") (pinfunction "RC4/D-/VM_15") (pintype "bidirectional"))
      (node (ref "USB") (pin "2") (pinfunction "2_2") (pintype "passive"))
    )
    (net (code "47") (name "Net-(IC3-RC5{slash}D+{slash}VP)") (class "Default")
      (node (ref "IC3") (pin "16") (pinfunction "RC5/D+/VP_16") (pintype "bidirectional"))
      (node (ref "USB") (pin "3") (pinfunction "3_3") (pintype "passive"))
    )
    (net (code "48") (name "Net-(IC3-RC6{slash}TX{slash}CK)") (class "Default")
      (node (ref "IC3") (pin "17") (pinfunction "RC6/TX/CK_17") (pintype "bidirectional"))
      (node (ref "R43") (pin "1") (pinfunction "1_1") (pintype "passive"))
    )
    (net (code "49") (name "Net-(IC3-RC7{slash}RX{slash}DT{slash}SDO)") (class "Default")
      (node (ref "IC3") (pin "18") (pinfunction "RC7/RX/DT/SDO_18") (pintype "bidirectional"))
      (node (ref "R24") (pin "1") (pinfunction "1_1") (pintype "passive"))
      (node (ref "USB/DOA") (pin "2") (pinfunction "2_2") (pintype "passive"))
    )
    (net (code "50") (name "Net-(IC3-VUSB)") (class "Default")
      (node (ref "C10") (pin "1") (pinfunction "1_1") (pintype "passive"))
      (node (ref "IC3") (pin "14") (pinfunction "VUSB_14") (pintype "bidirectional"))
    )
    (net (code "51") (name "Net-(IC3-~{MCLR}{slash}VPP{slash}RE3)") (class "Default")
      (node (ref "IC3") (pin "1") (pinfunction "~{MCLR}/VPP/RE3_1") (pintype "input"))
      (node (ref "R6") (pin "1") (pinfunction "1_1") (pintype "passive"))
      (node (ref "RST") (pin "3") (pinfunction "3_3") (pintype "passive"))
    )
    (net (code "52") (name "Net-(IC4A-+IN)") (class "Default")
      (node (ref "IC4") (pin "10") (pinfunction "+IN_10") (pintype "input"))
      (node (ref "IC4") (pin "14") (pinfunction "OUT_14") (pintype "output"))
      (node (ref "IC4") (pin "3") (pinfunction "+IN_3") (pintype "input"))
      (node (ref "IC4") (pin "5") (pinfunction "+IN_5") (pintype "input"))
      (node (ref "IC7") (pin "13") (pinfunction "X1_13") (pintype "bidirectional"))
      (node (ref "R19") (pin "2") (pinfunction "S_2") (pintype "passive"))
      (node (ref "R19") (pin "3") (pinfunction "A_3") (pintype "passive"))
      (node (ref "R21") (pin "1") (pinfunction "1_1") (pintype "passive"))
    )
    (net (code "53") (name "Net-(IC4A--IN)") (class "Default")
      (node (ref "IC4") (pin "1") (pinfunction "OUT_1") (pintype "output"))
      (node (ref "IC4") (pin "2") (pinfunction "-IN_2") (pintype "input"))
      (node (ref "IC7") (pin "1") (pinfunction "Y1_1") (pintype "bidirectional"))
      (node (ref "R22") (pin "1") (pinfunction "1_1") (pintype "passive"))
    )
    (net (code "54") (name "Net-(IC4B--IN)") (class "Default")
      (node (ref "IC4") (pin "6") (pinfunction "-IN_6") (pintype "input"))
      (node (ref "IC4") (pin "7") (pinfunction "OUT_7") (pintype "output"))
      (node (ref "IC7") (pin "3") (pinfunction "Z1_3") (pintype "bidirectional"))
      (node (ref "R23") (pin "1") (pinfunction "1_1") (pintype "passive"))
    )
    (net (code "55") (name "Net-(IC4C--IN)") (class "Default")
      (node (ref "IC4") (pin "8") (pinfunction "OUT_8") (pintype "output"))
      (node (ref "IC4") (pin "9") (pinfunction "-IN_9") (pintype "input"))
      (node (ref "SYNCHRO") (pin "2") (pinfunction "2_2") (pintype "passive"))
    )
    (net (code "56") (name "Net-(IC4D--IN)") (class "Default")
      (node (ref "IC4") (pin "13") (pinfunction "-IN_13") (pintype "input"))
      (node (ref "R13") (pin "2") (pinfunction "2_2") (pintype "passive"))
      (node (ref "R16") (pin "1") (pinfunction "1_1") (pintype "passive"))
    )
    (net (code "57") (name "Net-(IC5A--IN)") (class "Default")
      (node (ref "IC5") (pin "2") (pinfunction "-IN_2") (pintype "input"))
      (node (ref "R22") (pin "2") (pinfunction "2_2") (pintype "passive"))
      (node (ref "R26") (pin "1") (pinfunction "1_1") (pintype "passive"))
    )
    (net (code "58") (name "Net-(IC5A-OUT)") (class "Default")
      (node (ref "IC5") (pin "1") (pinfunction "OUT_1") (pintype "output"))
      (node (ref "IC7") (pin "2") (pinfunction "Y0_2") (pintype "bidirectional"))
      (node (ref "R26") (pin "2") (pinfunction "2_2") (pintype "passive"))
    )
    (net (code "59") (name "Net-(IC5B--IN)") (class "Default")
      (node (ref "IC5") (pin "6") (pinfunction "-IN_6") (pintype "input"))
      (node (ref "R36") (pin "2") (pinfunction "2_2") (pintype "passive"))
      (node (ref "R39") (pin "1") (pinfunction "1_1") (pintype "passive"))
    )
    (net (code "60") (name "Net-(IC5B-OUT)") (class "Default")
      (node (ref "IC5") (pin "7") (pinfunction "OUT_7") (pintype "output"))
      (node (ref "IC9") (pin "11") (pinfunction "CTRL_11") (pintype "input"))
      (node (ref "R39") (pin "2") (pinfunction "2_2") (pintype "passive"))
    )
    (net (code "61") (name "Net-(IC5C--IN)") (class "Default")
      (node (ref "IC5") (pin "9") (pinfunction "-IN_9") (pintype "input"))
      (node (ref "R21") (pin "2") (pinfunction "2_2") (pintype "passive"))
      (node (ref "R25") (pin "1") (pinfunction "1_1") (pintype "passive"))
    )
    (net (code "62") (name "Net-(IC5C-OUT)") (class "Default")
      (node (ref "IC5") (pin "8") (pinfunction "OUT_8") (pintype "output"))
      (node (ref "IC7") (pin "12") (pinfunction "X0_12") (pintype "bidirectional"))
      (node (ref "R25") (pin "2") (pinfunction "2_2") (pintype "passive"))
    )
    (net (code "63") (name "Net-(IC5D--IN)") (class "Default")
      (node (ref "IC5") (pin "13") (pinfunction "-IN_13") (pintype "input"))
      (node (ref "R23") (pin "2") (pinfunction "2_2") (pintype "passive"))
      (node (ref "R27") (pin "1") (pinfunction "1_1") (pintype "passive"))
    )
    (net (code "64") (name "Net-(IC5D-OUT)") (class "Default")
      (node (ref "IC5") (pin "14") (pinfunction "OUT_14") (pintype "output"))
      (node (ref "IC7") (pin "5") (pinfunction "Z0_5") (pintype "bidirectional"))
      (node (ref "R27") (pin "2") (pinfunction "2_2") (pintype "passive"))
    )
    (net (code "65") (name "Net-(IC6A--IN)") (class "Default")
      (node (ref "C22") (pin "1") (pinfunction "1_1") (pintype "passive"))
      (node (ref "IC6") (pin "2") (pinfunction "-IN_2") (pintype "input"))
      (node (ref "R28") (pin "2") (pinfunction "2_2") (pintype "passive"))
      (node (ref "R31") (pin "1") (pinfunction "1_1") (pintype "passive"))
    )
    (net (code "66") (name "Net-(IC6A-OUT)") (class "Default")
      (node (ref "C22") (pin "2") (pinfunction "2_2") (pintype "passive"))
      (node (ref "IC6") (pin "1") (pinfunction "OUT_1") (pintype "output"))
      (node (ref "R31") (pin "2") (pinfunction "2_2") (pintype "passive"))
      (node (ref "R34") (pin "1") (pinfunction "1_1") (pintype "passive"))
    )
    (net (code "67") (name "Net-(IC6B--IN)") (class "Default")
      (node (ref "C23") (pin "1") (pinfunction "1_1") (pintype "passive"))
      (node (ref "IC6") (pin "6") (pinfunction "-IN_6") (pintype "input"))
      (node (ref "R29") (pin "2") (pinfunction "2_2") (pintype "passive"))
      (node (ref "R32") (pin "1") (pinfunction "1_1") (pintype "passive"))
    )
    (net (code "68") (name "Net-(IC6B-OUT)") (class "Default")
      (node (ref "C23") (pin "2") (pinfunction "2_2") (pintype "passive"))
      (node (ref "IC6") (pin "7") (pinfunction "OUT_7") (pintype "output"))
      (node (ref "R32") (pin "2") (pinfunction "2_2") (pintype "passive"))
      (node (ref "R35") (pin "1") (pinfunction "1_1") (pintype "passive"))
    )
    (net (code "69") (name "Net-(IC6C--IN)") (class "Default")
      (node (ref "IC6") (pin "9") (pinfunction "-IN_9") (pintype "input"))
      (node (ref "R35") (pin "2") (pinfunction "2_2") (pintype "passive"))
      (node (ref "R38") (pin "1") (pinfunction "1_1") (pintype "passive"))
    )
    (net (code "70") (name "Net-(IC6C-OUT)") (class "Default")
      (node (ref "IC6") (pin "8") (pinfunction "OUT_8") (pintype "output"))
      (node (ref "IC9") (pin "6") (pinfunction "CTRL_6") (pintype "input"))
      (node (ref "R38") (pin "2") (pinfunction "2_2") (pintype "passive"))
    )
    (net (code "71") (name "Net-(IC6D--IN)") (class "Default")
      (node (ref "IC6") (pin "13") (pinfunction "-IN_13") (pintype "input"))
      (node (ref "R34") (pin "2") (pinfunction "2_2") (pintype "passive"))
      (node (ref "R37") (pin "1") (pinfunction "1_1") (pintype "passive"))
    )
    (net (code "72") (name "Net-(IC6D-OUT)") (class "Default")
      (node (ref "IC6") (pin "14") (pinfunction "OUT_14") (pintype "output"))
      (node (ref "IC9") (pin "3") (pinfunction "CTRL_3") (pintype "input"))
      (node (ref "R37") (pin "2") (pinfunction "2_2") (pintype "passive"))
    )
    (net (code "73") (name "Net-(IC7A-X)") (class "Default")
      (node (ref "IC7") (pin "14") (pinfunction "X_14") (pintype "bidirectional"))
      (node (ref "R40") (pin "1") (pinfunction "1_1") (pintype "passive"))
    )
    (net (code "74") (name "Net-(IC7A-Y)") (class "Default")
      (node (ref "IC7") (pin "15") (pinfunction "Y_15") (pintype "bidirectional"))
      (node (ref "R41") (pin "1") (pinfunction "1_1") (pintype "passive"))
    )
    (net (code "75") (name "Net-(IC7A-Z)") (class "Default")
      (node (ref "IC7") (pin "4") (pinfunction "Z_4") (pintype "bidirectional"))
      (node (ref "R42") (pin "1") (pinfunction "1_1") (pintype "passive"))
    )
    (net (code "76") (name "Net-(IC8A--IN)") (class "Default")
      (node (ref "C28") (pin "1") (pinfunction "1_1") (pintype "passive"))
      (node (ref "IC8") (pin "2") (pinfunction "-IN_2") (pintype "input"))
      (node (ref "R43") (pin "2") (pinfunction "2_2") (pintype "passive"))
      (node (ref "R47") (pin "1") (pinfunction "1_1") (pintype "passive"))
    )
    (net (code "77") (name "Net-(IC8A-OUT)") (class "Default")
      (node (ref "C28") (pin "2") (pinfunction "2_2") (pintype "passive"))
      (node (ref "CTR0") (pin "1") (pinfunction "1_1") (pintype "passive"))
      (node (ref "IC8") (pin "1") (pinfunction "OUT_1") (pintype "output"))
      (node (ref "R47") (pin "2") (pinfunction "2_2") (pintype "passive"))
      (node (ref "R48") (pin "1") (pinfunction "1_1") (pintype "passive"))
    )
    (net (code "78") (name "Net-(IC8B-+IN)") (class "Default")
      (node (ref "IC8") (pin "5") (pinfunction "+IN_5") (pintype "input"))
      (node (ref "R50") (pin "1") (pinfunction "1_1") (pintype "passive"))
    )
    (net (code "79") (name "Net-(IC8B--IN)") (class "Default")
      (node (ref "IC8") (pin "6") (pinfunction "-IN_6") (pintype "input"))
      (node (ref "R48") (pin "2") (pinfunction "2_2") (pintype "passive"))
      (node (ref "R55") (pin "1") (pinfunction "1_1") (pintype "passive"))
    )
    (net (code "80") (name "Net-(IC8B-OUT)") (class "Default")
      (node (ref "CTR0") (pin "3") (pinfunction "3_3") (pintype "passive"))
      (node (ref "IC8") (pin "7") (pinfunction "OUT_7") (pintype "output"))
      (node (ref "R55") (pin "2") (pinfunction "2_2") (pintype "passive"))
    )
    (net (code "81") (name "Net-(IC9A-IN)") (class "Default")
      (node (ref "IC9") (pin "2") (pinfunction "IN_2") (pintype "input"))
      (node (ref "R40") (pin "2") (pinfunction "2_2") (pintype "passive"))
      (node (ref "R44") (pin "2") (pinfunction "2_2") (pintype "passive"))
    )
    (net (code "82") (name "Net-(IC9B-IN)") (class "Default")
      (node (ref "IC9") (pin "7") (pinfunction "IN_7") (pintype "input"))
      (node (ref "R41") (pin "2") (pinfunction "2_2") (pintype "passive"))
      (node (ref "R45") (pin "2") (pinfunction "2_2") (pintype "passive"))
    )
    (net (code "83") (name "Net-(IC9C-IN)") (class "Default")
      (node (ref "IC9") (pin "10") (pinfunction "IN_10") (pintype "input"))
      (node (ref "R42") (pin "2") (pinfunction "2_2") (pintype "passive"))
      (node (ref "R46") (pin "2") (pinfunction "2_2") (pintype "passive"))
    )
    (net (code "84") (name "Net-(IC10A--IN)") (class "Default")
      (node (ref "C29") (pin "1") (pinfunction "1_1") (pintype "passive"))
      (node (ref "IC10") (pin "2") (pinfunction "-IN_2") (pintype "input"))
      (node (ref "IC9") (pin "4") (pinfunction "OUT_4") (pintype "output"))
      (node (ref "R51") (pin "1") (pinfunction "1_1") (pintype "passive"))
    )
    (net (code "85") (name "Net-(IC10A-OUT)") (class "Default")
      (node (ref "C29") (pin "2") (pinfunction "2_2") (pintype "passive"))
      (node (ref "IC10") (pin "1") (pinfunction "OUT_1") (pintype "output"))
      (node (ref "R51") (pin "2") (pinfunction "2_2") (pintype "passive"))
      (node (ref "SYNCHRO") (pin "5") (pinfunction "5_5") (pintype "passive"))
    )
    (net (code "86") (name "Net-(IC10B--IN)") (class "Default")
      (node (ref "C24") (pin "1") (pinfunction "1_1") (pintype "passive"))
      (node (ref "IC10") (pin "6") (pinfunction "-IN_6") (pintype "input"))
      (node (ref "R30") (pin "2") (pinfunction "2_2") (pintype "passive"))
      (node (ref "R33") (pin "1") (pinfunction "1_1") (pintype "passive"))
    )
    (net (code "87") (name "Net-(IC10B-OUT)") (class "Default")
      (node (ref "C24") (pin "2") (pinfunction "2_2") (pintype "passive"))
      (node (ref "IC10") (pin "7") (pinfunction "OUT_7") (pintype "output"))
      (node (ref "R33") (pin "2") (pinfunction "2_2") (pintype "passive"))
      (node (ref "R36") (pin "1") (pinfunction "1_1") (pintype "passive"))
    )
    (net (code "88") (name "Net-(IC10C--IN)") (class "Default")
      (node (ref "C30") (pin "1") (pinfunction "1_1") (pintype "passive"))
      (node (ref "IC10") (pin "9") (pinfunction "-IN_9") (pintype "input"))
      (node (ref "IC9") (pin "5") (pinfunction "OUT_5") (pintype "output"))
      (node (ref "R52") (pin "1") (pinfunction "1_1") (pintype "passive"))
    )
    (net (code "89") (name "Net-(IC10C-OUT)") (class "Default")
      (node (ref "C30") (pin "2") (pinfunction "2_2") (pintype "passive"))
      (node (ref "IC10") (pin "8") (pinfunction "OUT_8") (pintype "output"))
      (node (ref "R52") (pin "2") (pinfunction "2_2") (pintype "passive"))
      (node (ref "SYNCHRO") (pin "4") (pinfunction "4_4") (pintype "passive"))
    )
    (net (code "90") (name "Net-(IC10D--IN)") (class "Default")
      (node (ref "C31") (pin "1") (pinfunction "1_1") (pintype "passive"))
      (node (ref "IC10") (pin "13") (pinfunction "-IN_13") (pintype "input"))
      (node (ref "IC9") (pin "12") (pinfunction "OUT_12") (pintype "output"))
      (node (ref "R53") (pin "1") (pinfunction "1_1") (pintype "passive"))
    )
    (net (code "91") (name "Net-(IC10D-OUT)") (class "Default")
      (node (ref "C31") (pin "2") (pinfunction "2_2") (pintype "passive"))
      (node (ref "IC10") (pin "14") (pinfunction "OUT_14") (pintype "output"))
      (node (ref "R53") (pin "2") (pinfunction "2_2") (pintype "passive"))
      (node (ref "SYNCHRO") (pin "3") (pinfunction "3_3") (pintype "passive"))
    )
    (net (code "92") (name "Net-(R2-E)") (class "Default")
      (node (ref "C3") (pin "2") (pinfunction "2_2") (pintype "passive"))
      (node (ref "R2") (pin "1") (pinfunction "E_1") (pintype "passive"))
    )
    (net (code "93") (name "Net-(R5-Pad1)") (class "Default")
      (node (ref "R5") (pin "1") (pinfunction "1_1") (pintype "passive"))
      (node (ref "USB") (pin "1") (pinfunction "1_1") (pintype "passive"))
    )
    (net (code "94") (name "Net-(R13-Pad1)") (class "Default")
      (node (ref "R13") (pin "1") (pinfunction "1_1") (pintype "passive"))
      (node (ref "X1") (pin "4") (pinfunction "4_4") (pintype "passive"))
      (node (ref "X2") (pin "1") (pinfunction "1_1") (pintype "passive"))
      (node (ref "X2") (pin "3") (pinfunction "3_3") (pintype "passive"))
      (node (ref "X2") (pin "5") (pinfunction "5_5") (pintype "passive"))
    )
    (net (code "95") (name "Net-(R19-E)") (class "Default")
      (node (ref "R16") (pin "2") (pinfunction "2_2") (pintype "passive"))
      (node (ref "R19") (pin "1") (pinfunction "E_1") (pintype "passive"))
    )
    (net (code "96") (name "Net-(R56-Pad2)") (class "Default")
      (node (ref "R56") (pin "2") (pinfunction "2_2") (pintype "passive"))
      (node (ref "SV2") (pin "4") (pinfunction "4_4") (pintype "passive"))
    )
    (net (code "97") (name "unconnected-(IC1-ON1-Pad1)") (class "Default")
      (node (ref "IC1") (pin "1") (pinfunction "ON1_1") (pintype "passive"))
    )
    (net (code "98") (name "unconnected-(IC1-ON2-Pad5)") (class "Default")
      (node (ref "IC1") (pin "5") (pinfunction "ON2_5") (pintype "passive"))
    )
    (net (code "99") (name "unconnected-(IC1-OPT-Pad8)") (class "Default")
      (node (ref "IC1") (pin "8") (pinfunction "OPT_8") (pintype "passive"))
    )
    (net (code "100") (name "unconnected-(IC9D-CTRL-Pad14)") (class "Default")
      (node (ref "IC9") (pin "14") (pinfunction "CTRL_14") (pintype "input"))
    )
    (net (code "101") (name "unconnected-(IC9D-IN-Pad15)") (class "Default")
      (node (ref "IC9") (pin "15") (pinfunction "IN_15") (pintype "input"))
    )
    (net (code "102") (name "unconnected-(IC9D-OUT-Pad13)") (class "Default")
      (node (ref "IC9") (pin "13") (pinfunction "OUT_13") (pintype "output"))
    )
    (net (code "103") (name "unconnected-(IC9E-MODE-Pad1)") (class "Default")
      (node (ref "IC9") (pin "1") (pinfunction "MODE_1") (pintype "input"))
    )
  )
)
